# USB-FTDI.net
KiCad netlist of a schematic drawn in Altium Designer
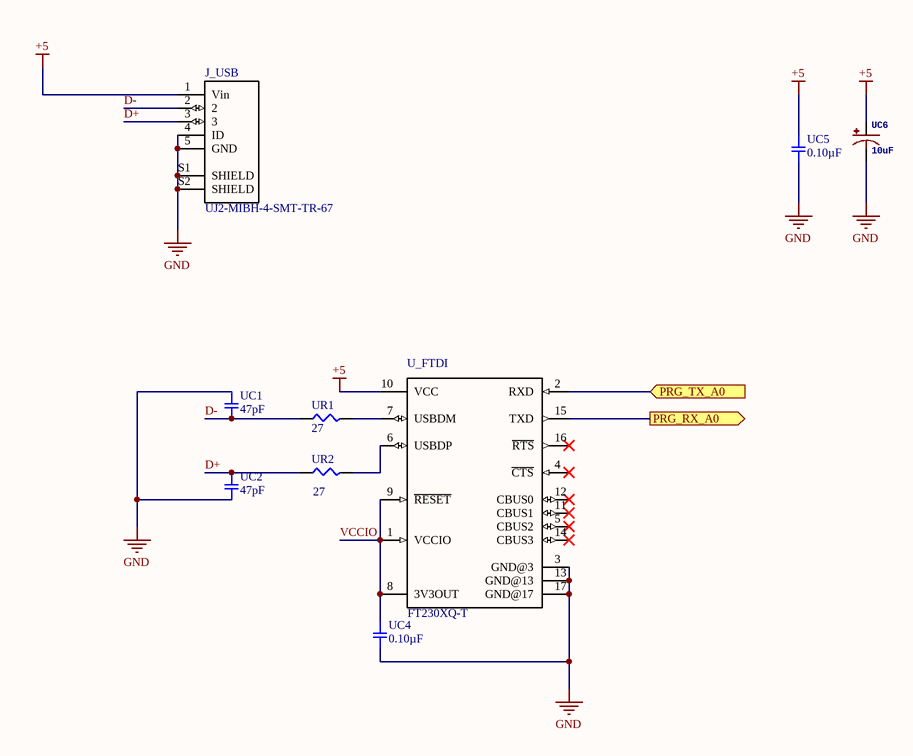
[diagram p0: USB-FTDI.SchDoc]

(export (version "E")
  (design (tool "Eeschema 10.0.6"))
  (components
    (comp (ref "J_USB")
      (value "UJ2-MIBH-4-SMT-TR-67")
      (footprint "*CUI_UJ2-MIBH-4-SMT-TR-67_UJ2-MIBH-4-SMT-TR-67(Primary)")
      (description "Micro B, USB 2.0, 1.8 A, Right Angle, Surface Mount _SMT_, Waterproof, USB Receptacle")
      (fields (field (name "MF") "CUI Devices") (field (name "DIGI-KEY_PART_NUMBER") "102-4970-1-ND"))
      (libsource (lib "UJ2-MIBH-4-SMT-TR-67") (part "UJ2-MIBH-4-SMT-TR-67"))
    )
    (comp (ref "UC1")
      (value "47pF")
      (footprint "SMD-0603C")
      (description "CAP CER 47PF 100V NP0 0603")
      (fields
        (field (name "DIGI-KEY PART NUMBER") "490-4944-1-ND")
        (field (name "PART NUMBER") "GCM1885C2A470JA16D")
      )
      (libsource (lib "capacitor_murata_0603") (part "GCM1885C2A470JA16D"))
    )
    (comp (ref "UC2")
      (value "47pF")
      (footprint "SMD-0603C")
      (description "CAP CER 47PF 100V NP0 0603")
      (fields
        (field (name "DIGI-KEY PART NUMBER") "490-4944-1-ND")
        (field (name "PART NUMBER") "GCM1885C2A470JA16D")
      )
      (libsource (lib "capacitor_murata_0603") (part "GCM1885C2A470JA16D"))
    )
    (comp (ref "UC4")
      (value "0.10µF")
      (footprint "SMD-0603C")
      (description "CAP CER 0.1UF 16V X7R 0603")
      (fields
        (field (name "DIGI-KEY PART NUMBER") "490-4774-1-ND")
        (field (name "PART NUMBER") "GCM188R71C104KA37D")
      )
      (libsource (lib "capacitor_murata_0603") (part "GCM188R71C104KA37D"))
    )
    (comp (ref "UC5")
      (value "0.10µF")
      (footprint "SMD-0603C")
      (description "CAP CER 0.1UF 16V X7R 0603")
      (fields
        (field (name "DIGI-KEY PART NUMBER") "490-4774-1-ND")
        (field (name "PART NUMBER") "GCM188R71C104KA37D")
      )
      (libsource (lib "capacitor_murata_0603") (part "GCM188R71C104KA37D"))
    )
    (comp (ref "UC6")
      (value "10uF")
      (footprint "0603-POLAR")
      (libsource (lib "SparkFun-Capacitors") (part "10UF-POLAR-0603-6.3V-20%(TANT)"))
    )
    (comp (ref "UR1")
      (value "27")
      (footprint "SMD-0603-RES")
      (description "RES SMD 27 OHM 1% 1/10W 0603")
      (fields
        (field (name "PART NUMBER") "ERJ-3EKF27R0V")
        (field (name "DIGI-KEY PART NUMBER") "P27.0HCT-ND")
      )
      (libsource (lib "Panasonic_ERJ_0603") (part "ERJ-3EKF27R0V"))
    )
    (comp (ref "UR2")
      (value "27")
      (footprint "SMD-0603-RES")
      (description "RES SMD 27 OHM 1% 1/10W 0603")
      (fields
        (field (name "PART NUMBER") "ERJ-3EKF27R0V")
        (field (name "DIGI-KEY PART NUMBER") "P27.0HCT-ND")
      )
      (libsource (lib "Panasonic_ERJ_0603") (part "ERJ-3EKF27R0V"))
    )
    (comp (ref "U_FTDI")
      (value "FT230XQ-T")
      (footprint "*QFN16")
      (description "USB Full Speed to Basic UART IC with USB Charger Detection, QFN-16")
      (fields (field (name "DIGI-KEY_PART_NUMBER") "768-1153-ND") (field (name "MF") "FTDI,"))
      (libsource (lib "FT230XQ-T") (part "FT230XQ-T"))
    )
  )
  (nets
    (net (code "1") (name "+5") (class "Default")
      (node (ref "J_USB") (pin "1") (pinfunction "Vin_1") (pintype "power_in"))
      (node (ref "UC5") (pin "1") (pinfunction "1_1") (pintype "passive"))
      (node (ref "UC6") (pin "+") (pinfunction "+_+") (pintype "passive"))
      (node (ref "U_FTDI") (pin "10") (pinfunction "VCC_10") (pintype "power_in"))
    )
    (net (code "2") (name "/D+") (class "Default")
      (node (ref "J_USB") (pin "3") (pinfunction "3_3") (pintype "bidirectional"))
      (node (ref "UC2") (pin "1") (pinfunction "1_1") (pintype "passive"))
      (node (ref "UR2") (pin "1") (pinfunction "1_1") (pintype "passive"))
    )
    (net (code "3") (name "/D-") (class "Default")
      (node (ref "J_USB") (pin "2") (pinfunction "2_2") (pintype "bidirectional"))
      (node (ref "UC1") (pin "2") (pinfunction "2_2") (pintype "passive"))
      (node (ref "UR1") (pin "1") (pinfunction "1_1") (pintype "passive"))
    )
    (net (code "4") (name "/PRG_RX_A0") (class "Default")
      (node (ref "U_FTDI") (pin "15") (pinfunction "TXD_15") (pintype "output"))
    )
    (net (code "5") (name "/PRG_TX_A0") (class "Default")
      (node (ref "U_FTDI") (pin "2") (pinfunction "RXD_2") (pintype "input"))
    )
    (net (code "6") (name "/VCCIO") (class "Default")
      (node (ref "UC4") (pin "1") (pinfunction "1_1") (pintype "passive"))
      (node (ref "U_FTDI") (pin "1") (pinfunction "VCCIO_1") (pintype "input"))
      (node (ref "U_FTDI") (pin "8") (pinfunction "3V3OUT_8") (pintype "passive"))
      (node (ref "U_FTDI") (pin "9") (pinfunction "~{RESET}_9") (pintype "input"))
    )
    (net (code "7") (name "GND") (class "Default")
      (node (ref "J_USB") (pin "4") (pinfunction "ID_4") (pintype "power_in"))
      (node (ref "J_USB") (pin "5") (pinfunction "GND_5") (pintype "power_in"))
      (node (ref "J_USB") (pin "S1") (pinfunction "SHIELD_S1") (pintype "power_in"))
      (node (ref "J_USB") (pin "S2") (pinfunction "SHIELD_S2") (pintype "power_in"))
      (node (ref "UC1") (pin "1") (pinfunction "1_1") (pintype "passive"))
      (node (ref "UC2") (pin "2") (pinfunction "2_2") (pintype "passive"))
      (node (ref "UC4") (pin "2") (pinfunction "2_2") (pintype "passive"))
      (node (ref "UC5") (pin "2") (pinfunction "2_2") (pintype "passive"))
      (node (ref "UC6") (pin "-") (pinfunction "-_-") (pintype "passive"))
      (node (ref "U_FTDI") (pin "13") (pinfunction "GND@13_13") (pintype "power_in"))
      (node (ref "U_FTDI") (pin "17") (pinfunction "GND@17_17") (pintype "power_in"))
      (node (ref "U_FTDI") (pin "3") (pinfunction "GND@3_3") (pintype "power_in"))
    )
    (net (code "8") (name "Net-(U_FTDI-USBDM)") (class "Default")
      (node (ref "UR1") (pin "2") (pinfunction "2_2") (pintype "passive"))
      (node (ref "U_FTDI") (pin "7") (pinfunction "USBDM_7") (pintype "bidirectional"))
    )
    (net (code "9") (name "Net-(U_FTDI-USBDP)") (class "Default")
      (node (ref "UR2") (pin "2") (pinfunction "2_2") (pintype "passive"))
      (node (ref "U_FTDI") (pin "6") (pinfunction "USBDP_6") (pintype "bidirectional"))
    )
    (net (code "10") (name "unconnected-(U_FTDI-CBUS0-Pad12)") (class "Default")
      (node (ref "U_FTDI") (pin "12") (pinfunction "CBUS0_12") (pintype "bidirectional+no_connect"))
    )
    (net (code "11") (name "unconnected-(U_FTDI-CBUS1-Pad11)") (class "Default")
      (node (ref "U_FTDI") (pin "11") (pinfunction "CBUS1_11") (pintype "bidirectional+no_connect"))
    )
    (net (code "12") (name "unconnected-(U_FTDI-CBUS2-Pad5)") (class "Default")
      (node (ref "U_FTDI") (pin "5") (pinfunction "CBUS2_5") (pintype "bidirectional+no_connect"))
    )
    (net (code "13") (name "unconnected-(U_FTDI-CBUS3-Pad14)") (class "Default")
      (node (ref "U_FTDI") (pin "14") (pinfunction "CBUS3_14") (pintype "bidirectional+no_connect"))
    )
    (net (code "14") (name "unconnected-(U_FTDI-~{CTS}-Pad4)") (class "Default")
      (node (ref "U_FTDI") (pin "4") (pinfunction "~{CTS}_4") (pintype "input+no_connect"))
    )
    (net (code "15") (name "unconnected-(U_FTDI-~{RTS}-Pad16)") (class "Default")
      (node (ref "U_FTDI") (pin "16") (pinfunction "~{RTS}_16") (pintype "output+no_connect"))
    )
  )
)
